# MicroController.net
KiCad netlist of a schematic drawn in Altium Designer
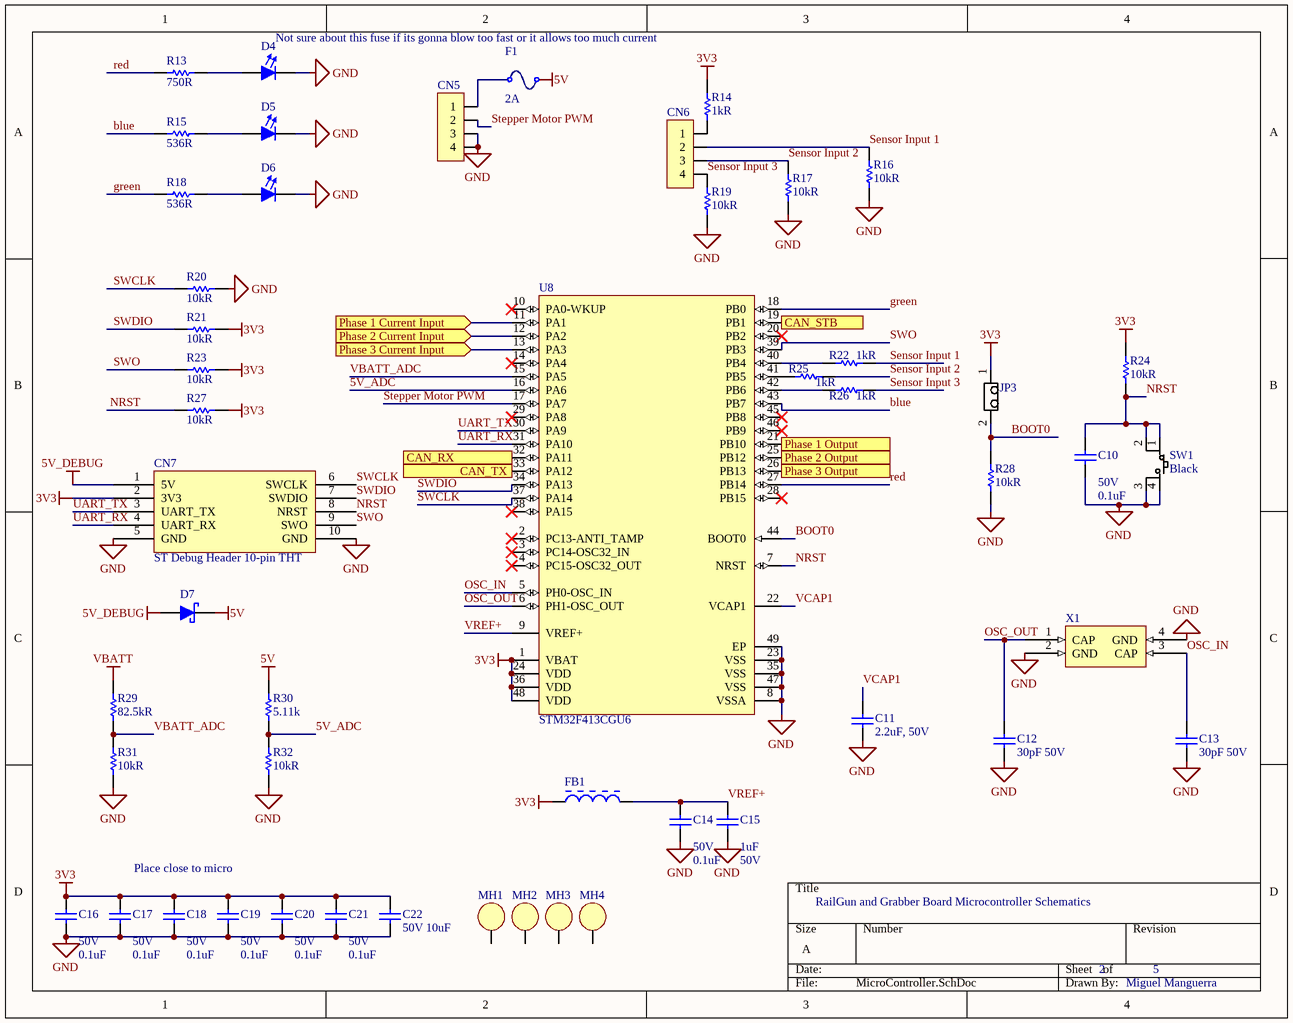
[diagram p0: MicroController.SchDoc]

(export (version "E")
  (design (tool "Eeschema 10.0.6"))
  (components
    (comp (ref "C10")
      (value "CL10B104JB8NNNC")
      (footprint "FP-CL10-0_1-MFG")
      (description "CAP CER 0.1UF 50V X7R 0603")
      (fields
        (field (name "TOLERANCE") "5%")
        (field (name "VOLTAGE") "50V")
        (field (name "CAPACITANCE") "0.1uF")
      )
      (libsource (lib "AUVIC") (part "CAP-NP-2"))
    )
    (comp (ref "C11")
      (value "2.2uF, 50V")
      (footprint "CAPC1608N(0603\")")
      (description "Capacitor, Ceramic, 50V, 10%, 0603 SMD, X5R")
      (fields (field (name "MADE BY") "*") (field (name "PUBLISHER") "AUVic"))
      (libsource (lib "") (part "Symbol_7"))
    )
    (comp (ref "C12")
      (value "30pF 50V")
      (footprint "CAPC1608N(0603\")")
      (description "Capacitor, Ceramic, 50V, +/-1%, 0603 SMD, C0G")
      (fields (field (name "MADE BY") "Andy Bates") (field (name "PUBLISHER") "AUVic"))
      (libsource (lib "") (part "Symbol_8"))
    )
    (comp (ref "C13")
      (value "30pF 50V")
      (footprint "CAPC1608N(0603\")")
      (description "Capacitor, Ceramic, 50V, +/-1%, 0603 SMD, C0G")
      (fields (field (name "MADE BY") "Andy Bates") (field (name "PUBLISHER") "AUVic"))
      (libsource (lib "") (part "Symbol_8"))
    )
    (comp (ref "C14")
      (value "CL10B104JB8NNNC")
      (footprint "FP-CL10-0_1-MFG")
      (description "CAP CER 0.1UF 50V X7R 0603")
      (fields
        (field (name "TOLERANCE") "5%")
        (field (name "VOLTAGE") "50V")
        (field (name "CAPACITANCE") "0.1uF")
      )
      (libsource (lib "AUVIC") (part "CAP-NP-2"))
    )
    (comp (ref "C15")
      (value "CL21B105KBFNNNG")
      (footprint "0803 CAP")
      (description "SAMSUNG ELECTRO-MECHANICS - CL21B105KBFNNNG - MLCC CAPACITORS")
      (fields
        (field (name "TOLERANCE") "10%")
        (field (name "CAPACITANCE") "1uF")
        (field (name "VOLTAGE") "50V")
      )
      (libsource (lib "") (part "Symbol_4"))
    )
    (comp (ref "C16")
      (value "CL10B104JB8NNNC")
      (footprint "FP-CL10-0_1-MFG")
      (description "CAP CER 0.1UF 50V X7R 0603")
      (fields
        (field (name "TOLERANCE") "5%")
        (field (name "VOLTAGE") "50V")
        (field (name "CAPACITANCE") "0.1uF")
      )
      (libsource (lib "AUVIC") (part "CAP-NP-2"))
    )
    (comp (ref "C17")
      (value "CL10B104JB8NNNC")
      (footprint "FP-CL10-0_1-MFG")
      (description "CAP CER 0.1UF 50V X7R 0603")
      (fields
        (field (name "TOLERANCE") "5%")
        (field (name "VOLTAGE") "50V")
        (field (name "CAPACITANCE") "0.1uF")
      )
      (libsource (lib "AUVIC") (part "CAP-NP-2"))
    )
    (comp (ref "C18")
      (value "CL10B104JB8NNNC")
      (footprint "FP-CL10-0_1-MFG")
      (description "CAP CER 0.1UF 50V X7R 0603")
      (fields
        (field (name "TOLERANCE") "5%")
        (field (name "VOLTAGE") "50V")
        (field (name "CAPACITANCE") "0.1uF")
      )
      (libsource (lib "AUVIC") (part "CAP-NP-2"))
    )
    (comp (ref "C19")
      (value "CL10B104JB8NNNC")
      (footprint "FP-CL10-0_1-MFG")
      (description "CAP CER 0.1UF 50V X7R 0603")
      (fields
        (field (name "TOLERANCE") "5%")
        (field (name "VOLTAGE") "50V")
        (field (name "CAPACITANCE") "0.1uF")
      )
      (libsource (lib "AUVIC") (part "CAP-NP-2"))
    )
    (comp (ref "C20")
      (value "CL10B104JB8NNNC")
      (footprint "FP-CL10-0_1-MFG")
      (description "CAP CER 0.1UF 50V X7R 0603")
      (fields
        (field (name "TOLERANCE") "5%")
        (field (name "VOLTAGE") "50V")
        (field (name "CAPACITANCE") "0.1uF")
      )
      (libsource (lib "AUVIC") (part "CAP-NP-2"))
    )
    (comp (ref "C21")
      (value "CL10B104JB8NNNC")
      (footprint "FP-CL10-0_1-MFG")
      (description "CAP CER 0.1UF 50V X7R 0603")
      (fields
        (field (name "TOLERANCE") "5%")
        (field (name "VOLTAGE") "50V")
        (field (name "CAPACITANCE") "0.1uF")
      )
      (libsource (lib "AUVIC") (part "CAP-NP-2"))
    )
    (comp (ref "C22")
      (value "50V 10uF")
      (footprint "CAPC3216X180X50LL20T30")
      (description "Cap Ceramic 10uF 50V X7R 10% Pad SMD 1206 125°C T/R")
      (fields (field (name "TOLERANCE") "10%"))
      (libsource (lib "AUVIC") (part "CAP-NP-2"))
    )
    (comp (ref "CN5")
      (value "Header, Male, 1x4, RA, Pitch 0.1\" (2.54mm)")
      (footprint "HEADER, MALE, SHROUDED, 4x1, PITCH 0.1\" (2.54mm), RA")
      (description "Connector Header Through Hole, Right Angle 4 position 0.100\" (2.54mm)")
      (fields (field (name "CREATED BY") "Miguel Manguerra"))
      (libsource (lib "") (part "Symbol_3"))
    )
    (comp (ref "CN6")
      (value "Header, Male, 1x4, RA, Pitch 0.1\" (2.54mm)")
      (footprint "HEADER, MALE, SHROUDED, 4x1, PITCH 0.1\" (2.54mm), RA")
      (description "Connector Header Through Hole, Right Angle 4 position 0.100\" (2.54mm)")
      (fields (field (name "CREATED BY") "Miguel Manguerra"))
      (libsource (lib "") (part "Symbol_3"))
    )
    (comp (ref "CN7")
      (value "ST Debug Header 10-pin THT")
      (footprint "10-pin shrouded header THT")
      (description "CONN HEADER VERT 10POS 2.54MM")
      (libsource (lib "AUVIC") (part "ST Debug Header 10-pin"))
    )
    (comp (ref "D4")
      (value "LSQ976-NR-1")
      (footprint "FP-LB_Q39E-MFG")
      (description "LED Red 645nm 2-Pin Chip 0603(1608Metric) T/R")
      (libsource (lib "AUVIC") (part "Symbol"))
    )
    (comp (ref "D5")
      (value "LBQ39E-N1OO-35-1")
      (footprint "FP-LB_Q39E-MFG")
      (description "LED BLUE DIFFUSED 0603 SMD")
      (libsource (lib "AUVIC") (part "Symbol"))
    )
    (comp (ref "D6")
      (value "LT Q39G-Q1OO-25-1")
      (footprint "FP-LB_Q39E-MFG")
      (description "LED GREEN DIFFUSED 0603 SMD")
      (libsource (lib "AUVIC") (part "Symbol"))
    )
    (comp (ref "D7")
      (value "CUS08F30,H3F")
      (footprint "SC-76")
      (description "Diode Schottky 30V 800mA Surface Mount USC")
      (libsource (lib "") (part "Symbol_6"))
    )
    (comp (ref "F1")
      (value "SMD Fuse, 2A, 63V,")
      (footprint "1206 SMD")
      (fields (field (name "CURRENT") "2A") (field (name "CREATED BY") "Poorna Chander Kalidas"))
      (libsource (lib "") (part "Symbol_2"))
    )
    (comp (ref "FB1")
      (value "BLM18AG601SN1D")
      (footprint "MURA-BLM18-F-H1-CHIP-2_V")
      (fields (field (name "TOLERANCE") "25%"))
      (libsource (lib "AUVIC") (part "MURA-FB-2"))
    )
    (comp (ref "JP3")
      (value "1x2 Male Header")
      (footprint "2X1 Males Header")
      (fields (field (name "MADE BY") "Andy Bates"))
      (libsource (lib "AUVIC") (part "1x2 Male Header"))
    )
    (comp (ref "MH1")
      (value "Mount_Hole_3mm")
      (footprint "Mount-Hole_3mm")
      (description "Mounting hold for M3 hex standoff")
      (libsource (lib "AUVIC") (part "Mount_Hole_3mm"))
    )
    (comp (ref "MH2")
      (value "Mount_Hole_3mm")
      (footprint "Mount-Hole_3mm")
      (description "Mounting hold for M3 hex standoff")
      (libsource (lib "AUVIC") (part "Mount_Hole_3mm"))
    )
    (comp (ref "MH3")
      (value "Mount_Hole_3mm")
      (footprint "Mount-Hole_3mm")
      (description "Mounting hold for M3 hex standoff")
      (libsource (lib "AUVIC") (part "Mount_Hole_3mm"))
    )
    (comp (ref "MH4")
      (value "Mount_Hole_3mm")
      (footprint "Mount-Hole_3mm")
      (description "Mounting hold for M3 hex standoff")
      (libsource (lib "AUVIC") (part "Mount_Hole_3mm"))
    )
    (comp (ref "R13")
      (value "750R")
      (footprint "RESC0603(1608)_N")
      (description "Res Thick Film 0603 750 Ohm 1% 0.1W(1/10W) ±100ppm/C Epoxy SMD T/R")
      (fields (field (name "TOLERANCE") "1%"))
      (libsource (lib "AUVIC") (part "RES"))
    )
    (comp (ref "R14")
      (value "1kR")
      (footprint "RESC1608N(0603\")")
      (description "1kR, 1%, 1/10W , 0603, SMD")
      (fields (field (name "PUBLISHER") "AUVic") (field (name "CREATED BY") "Andy Bates"))
      (libsource (lib "") (part "Symbol_1"))
    )
    (comp (ref "R15")
      (value "536R")
      (footprint "RESC1608X55X30LL15T15")
      (description "SMD Chip Resistor, 0603 [1608 Metric], 536 ohm, ERJ3EK Series, 75 V, Thick Film, 100 mW")
      (fields (field (name "TOLERANCE") "1%"))
      (libsource (lib "AUVIC") (part "RES"))
    )
    (comp (ref "R16")
      (value "10kR")
      (footprint "RESC1608N(0603\")")
      (description "10kR, 1%, 1/10W, 0603 SMD")
      (fields (field (name "MADE BY") "Ashwin Sira"))
      (libsource (lib "") (part "Symbol_1"))
    )
    (comp (ref "R17")
      (value "10kR")
      (footprint "RESC1608N(0603\")")
      (description "10kR, 1%, 1/10W, 0603 SMD")
      (fields (field (name "MADE BY") "Ashwin Sira"))
      (libsource (lib "") (part "Symbol_1"))
    )
    (comp (ref "R18")
      (value "536R")
      (footprint "RESC1608X55X30LL15T15")
      (description "SMD Chip Resistor, 0603 [1608 Metric], 536 ohm, ERJ3EK Series, 75 V, Thick Film, 100 mW")
      (fields (field (name "TOLERANCE") "1%"))
      (libsource (lib "AUVIC") (part "RES"))
    )
    (comp (ref "R19")
      (value "10kR")
      (footprint "RESC1608N(0603\")")
      (description "10kR, 1%, 1/10W, 0603 SMD")
      (fields (field (name "MADE BY") "Ashwin Sira"))
      (libsource (lib "") (part "Symbol_1"))
    )
    (comp (ref "R20")
      (value "10kR")
      (footprint "RESC1608N(0603\")")
      (description "10kR, 1%, 1/10W, 0603 SMD")
      (fields (field (name "MADE BY") "Ashwin Sira"))
      (libsource (lib "") (part "Symbol_1"))
    )
    (comp (ref "R21")
      (value "10kR")
      (footprint "RESC1608N(0603\")")
      (description "10kR, 1%, 1/10W, 0603 SMD")
      (fields (field (name "MADE BY") "Ashwin Sira"))
      (libsource (lib "") (part "Symbol_1"))
    )
    (comp (ref "R22")
      (value "1kR")
      (footprint "RESC1608N(0603\")")
      (description "1kR, 1%, 1/10W , 0603, SMD")
      (fields (field (name "PUBLISHER") "AUVic") (field (name "CREATED BY") "Andy Bates"))
      (libsource (lib "") (part "Symbol_1"))
    )
    (comp (ref "R23")
      (value "10kR")
      (footprint "RESC1608N(0603\")")
      (description "10kR, 1%, 1/10W, 0603 SMD")
      (fields (field (name "MADE BY") "Ashwin Sira"))
      (libsource (lib "") (part "Symbol_1"))
    )
    (comp (ref "R24")
      (value "10kR")
      (footprint "RESC1608N(0603\")")
      (description "10kR, 1%, 1/10W, 0603 SMD")
      (fields (field (name "MADE BY") "Ashwin Sira"))
      (libsource (lib "") (part "Symbol_1"))
    )
    (comp (ref "R25")
      (value "1kR")
      (footprint "RESC1608N(0603\")")
      (description "1kR, 1%, 1/10W , 0603, SMD")
      (fields (field (name "PUBLISHER") "AUVic") (field (name "CREATED BY") "Andy Bates"))
      (libsource (lib "") (part "Symbol_1"))
    )
    (comp (ref "R26")
      (value "1kR")
      (footprint "RESC1608N(0603\")")
      (description "1kR, 1%, 1/10W , 0603, SMD")
      (fields (field (name "PUBLISHER") "AUVic") (field (name "CREATED BY") "Andy Bates"))
      (libsource (lib "") (part "Symbol_1"))
    )
    (comp (ref "R27")
      (value "10kR")
      (footprint "RESC1608N(0603\")")
      (description "10kR, 1%, 1/10W, 0603 SMD")
      (fields (field (name "MADE BY") "Ashwin Sira"))
      (libsource (lib "") (part "Symbol_1"))
    )
    (comp (ref "R28")
      (value "10kR")
      (footprint "RESC1608N(0603\")")
      (description "10kR, 1%, 1/10W, 0603 SMD")
      (fields (field (name "MADE BY") "Ashwin Sira"))
      (libsource (lib "") (part "Symbol_1"))
    )
    (comp (ref "R29")
      (value "ERJ-3EKF8252V")
      (footprint "RESC1608X55X30LL15T15")
      (description "RES SMD 82.5K OHM 1% 1/10W 0603")
      (fields (field (name "RESISTANCE") "82.5kR") (field (name "TOLERANCE") "1%"))
      (libsource (lib "AUVIC") (part "RES"))
    )
    (comp (ref "R30")
      (value "5.11k")
      (footprint "RESC1608N(0603\")")
      (description "Resistance, Tolerance, Power, 0603, SMD/THT")
      (fields
        (field (name "Comment") "5.11kR, 1%, 1/10W, 0603, SMD")
        (field (name "PUBLISHER") "AUVic")
        (field (name "CREATED BY") "Jordan Day")
      )
      (libsource (lib "") (part "Symbol_1"))
    )
    (comp (ref "R31")
      (value "RC0603FR-0710KL")
      (footprint "RESC1608X55X25NL10T15")
      (description "Res General Purpose Thick Film 0603 10K Ohm 1% 1/10W ±100ppm/°C Molded SMD Paper T/R")
      (fields (field (name "RESISTANCE") "10kR") (field (name "TOLERANCE") "1%"))
      (libsource (lib "AUVIC") (part "RES-2"))
    )
    (comp (ref "R32")
      (value "RC0603FR-0710KL")
      (footprint "RESC1608X55X25NL10T15")
      (description "Res General Purpose Thick Film 0603 10K Ohm 1% 1/10W ±100ppm/°C Molded SMD Paper T/R")
      (fields (field (name "RESISTANCE") "10kR") (field (name "TOLERANCE") "1%"))
      (libsource (lib "AUVIC") (part "RES-2"))
    )
    (comp (ref "SW1")
      (value "PTS645SL43SMTR92LFS")
      (footprint "4-SPST-NO")
      (description "Black Switch Tactile N.O. SPST Round Button Gull Wing 0.05A 12VDC 100000Cycles 1.27N SMD T/R")
      (fields (field (name "BUTTON COLOUR") "Black"))
      (libsource (lib "") (part "Symbol_5"))
    )
    (comp (ref "U8")
      (value "STM32F413CGU6")
      (footprint "STM-UFQFPN48_N")
      (description "MCU 32-Bit STM32 ARM Cortex M4 RISC 1MB Flash 1.8V/2.5V/3.3V 48-Pin UFQFPN Tray")
      (libsource (lib "AUVIC") (part "MC-ARM-STM32F411-UFQFPN48"))
    )
    (comp (ref "X1")
      (value "CRYSTAL 8.0MHZ 16PF SMD")
      (footprint "QFN250P750X520X140_HS-5M")
      (description "8MHz ±30ppm Crystal 16pF 80 Ohms 4-SMD, No Lead")
      (libsource (lib "AUVIC") (part "LFXTAL026380REEL"))
    )
  )
  (nets
    (net (code "1") (name "/5V_ADC") (class "Default")
      (node (ref "R30") (pin "2") (pinfunction "2_2") (pintype "passive"))
      (node (ref "R32") (pin "1") (pinfunction "1_1") (pintype "passive"))
      (node (ref "U8") (pin "16") (pinfunction "PA6_16") (pintype "bidirectional"))
    )
    (net (code "2") (name "/BOOT0") (class "Default")
      (node (ref "JP3") (pin "2") (pinfunction "2_2") (pintype "passive"))
      (node (ref "R28") (pin "1") (pinfunction "1_1") (pintype "passive"))
      (node (ref "U8") (pin "44") (pinfunction "BOOT0_44") (pintype "input"))
    )
    (net (code "3") (name "/CAN_RX") (class "Default")
      (node (ref "U8") (pin "32") (pinfunction "PA11_32") (pintype "bidirectional"))
    )
    (net (code "4") (name "/CAN_STB") (class "Default")
      (node (ref "U8") (pin "19") (pinfunction "PB1_19") (pintype "bidirectional"))
    )
    (net (code "5") (name "/CAN_TX") (class "Default")
      (node (ref "U8") (pin "33") (pinfunction "PA12_33") (pintype "bidirectional"))
    )
    (net (code "6") (name "/NRST") (class "Default")
      (node (ref "C10") (pin "1") (pinfunction "1_1") (pintype "passive"))
      (node (ref "CN7") (pin "8") (pinfunction "NRST_8") (pintype "passive"))
      (node (ref "R24") (pin "2") (pinfunction "2_2") (pintype "passive"))
      (node (ref "R27") (pin "2") (pinfunction "2_2") (pintype "passive"))
      (node (ref "SW1") (pin "1") (pinfunction "1_1") (pintype "passive"))
      (node (ref "SW1") (pin "2") (pinfunction "2_2") (pintype "passive"))
      (node (ref "U8") (pin "7") (pinfunction "NRST_7") (pintype "bidirectional"))
    )
    (net (code "7") (name "/OSC_IN") (class "Default")
      (node (ref "C13") (pin "1") (pinfunction "1_1") (pintype "passive"))
      (node (ref "U8") (pin "5") (pinfunction "PH0-OSC_IN_5") (pintype "bidirectional"))
      (node (ref "X1") (pin "3") (pinfunction "CAP_3") (pintype "input"))
    )
    (net (code "8") (name "/OSC_OUT") (class "Default")
      (node (ref "C12") (pin "1") (pinfunction "1_1") (pintype "passive"))
      (node (ref "U8") (pin "6") (pinfunction "PH1-OSC_OUT_6") (pintype "bidirectional"))
      (node (ref "X1") (pin "1") (pinfunction "CAP_1") (pintype "input"))
    )
    (net (code "9") (name "/Phase 1 Current Input") (class "Default")
      (node (ref "U8") (pin "11") (pinfunction "PA1_11") (pintype "bidirectional"))
    )
    (net (code "10") (name "/Phase 1 Output") (class "Default")
      (node (ref "U8") (pin "21") (pinfunction "PB10_21") (pintype "bidirectional"))
    )
    (net (code "11") (name "/Phase 2 Current Input") (class "Default")
      (node (ref "U8") (pin "12") (pinfunction "PA2_12") (pintype "bidirectional"))
    )
    (net (code "12") (name "/Phase 2 Output") (class "Default")
      (node (ref "U8") (pin "25") (pinfunction "PB12_25") (pintype "bidirectional"))
    )
    (net (code "13") (name "/Phase 3 Current Input") (class "Default")
      (node (ref "U8") (pin "13") (pinfunction "PA3_13") (pintype "bidirectional"))
    )
    (net (code "14") (name "/Phase 3 Output") (class "Default")
      (node (ref "U8") (pin "26") (pinfunction "PB13_26") (pintype "bidirectional"))
    )
    (net (code "15") (name "/SWCLK") (class "Default")
      (node (ref "CN7") (pin "6") (pinfunction "SWCLK_6") (pintype "passive"))
      (node (ref "R20") (pin "2") (pinfunction "2_2") (pintype "passive"))
      (node (ref "U8") (pin "37") (pinfunction "PA14_37") (pintype "bidirectional"))
    )
    (net (code "16") (name "/SWDIO") (class "Default")
      (node (ref "CN7") (pin "7") (pinfunction "SWDIO_7") (pintype "passive"))
      (node (ref "R21") (pin "2") (pinfunction "2_2") (pintype "passive"))
      (node (ref "U8") (pin "34") (pinfunction "PA13_34") (pintype "bidirectional"))
    )
    (net (code "17") (name "/SWO") (class "Default")
      (node (ref "CN7") (pin "9") (pinfunction "SWO_9") (pintype "passive"))
      (node (ref "R23") (pin "2") (pinfunction "2_2") (pintype "passive"))
      (node (ref "U8") (pin "39") (pinfunction "PB3_39") (pintype "bidirectional"))
    )
    (net (code "18") (name "/Sensor Input 1") (class "Default")
      (node (ref "CN6") (pin "2") (pinfunction "2_2") (pintype "passive"))
      (node (ref "R16") (pin "1") (pinfunction "1_1") (pintype "passive"))
      (node (ref "R22") (pin "2") (pinfunction "2_2") (pintype "passive"))
    )
    (net (code "19") (name "/Sensor Input 2") (class "Default")
      (node (ref "CN6") (pin "3") (pinfunction "3_3") (pintype "passive"))
      (node (ref "R17") (pin "1") (pinfunction "1_1") (pintype "passive"))
      (node (ref "R25") (pin "2") (pinfunction "2_2") (pintype "passive"))
    )
    (net (code "20") (name "/Sensor Input 3") (class "Default")
      (node (ref "CN6") (pin "4") (pinfunction "4_4") (pintype "passive"))
      (node (ref "R19") (pin "1") (pinfunction "1_1") (pintype "passive"))
      (node (ref "R26") (pin "2") (pinfunction "2_2") (pintype "passive"))
    )
    (net (code "21") (name "/Stepper Motor PWM") (class "Default")
      (node (ref "CN5") (pin "2") (pinfunction "2_2") (pintype "passive"))
      (node (ref "U8") (pin "17") (pinfunction "PA7_17") (pintype "bidirectional"))
    )
    (net (code "22") (name "/UART_RX") (class "Default")
      (node (ref "CN7") (pin "4") (pinfunction "UART_RX_4") (pintype "passive"))
      (node (ref "U8") (pin "31") (pinfunction "PA10_31") (pintype "bidirectional"))
    )
    (net (code "23") (name "/UART_TX") (class "Default")
      (node (ref "CN7") (pin "3") (pinfunction "UART_TX_3") (pintype "passive"))
      (node (ref "U8") (pin "30") (pinfunction "PA9_30") (pintype "bidirectional"))
    )
    (net (code "24") (name "/VBATT_ADC") (class "Default")
      (node (ref "R29") (pin "2") (pinfunction "2_2") (pintype "passive"))
      (node (ref "R31") (pin "1") (pinfunction "1_1") (pintype "passive"))
      (node (ref "U8") (pin "15") (pinfunction "PA5_15") (pintype "bidirectional"))
    )
    (net (code "25") (name "/VCAP1") (class "Default")
      (node (ref "C11") (pin "1") (pinfunction "Anode_1") (pintype "passive"))
      (node (ref "U8") (pin "22") (pinfunction "VCAP1_22") (pintype "passive"))
    )
    (net (code "26") (name "/VREF+") (class "Default")
      (node (ref "C14") (pin "1") (pinfunction "1_1") (pintype "passive"))
      (node (ref "C15") (pin "1") (pinfunction "1_1") (pintype "passive"))
      (node (ref "FB1") (pin "2") (pinfunction "2_2") (pintype "passive"))
      (node (ref "U8") (pin "9") (pinfunction "VREF+_9") (pintype "power_in"))
    )
    (net (code "27") (name "/blue") (class "Default")
      (node (ref "R15") (pin "1") (pinfunction "1_1") (pintype "passive"))
      (node (ref "U8") (pin "43") (pinfunction "PB7_43") (pintype "bidirectional"))
    )
    (net (code "28") (name "/green") (class "Default")
      (node (ref "R18") (pin "1") (pinfunction "1_1") (pintype "passive"))
      (node (ref "U8") (pin "18") (pinfunction "PB0_18") (pintype "bidirectional"))
    )
    (net (code "29") (name "/red") (class "Default")
      (node (ref "R13") (pin "1") (pinfunction "1_1") (pintype "passive"))
      (node (ref "U8") (pin "27") (pinfunction "PB14_27") (pintype "bidirectional"))
    )
    (net (code "30") (name "3V3") (class "Default")
      (node (ref "C16") (pin "1") (pinfunction "1_1") (pintype "passive"))
      (node (ref "C17") (pin "1") (pinfunction "1_1") (pintype "passive"))
      (node (ref "C18") (pin "1") (pinfunction "1_1") (pintype "passive"))
      (node (ref "C19") (pin "1") (pinfunction "1_1") (pintype "passive"))
      (node (ref "C20") (pin "1") (pinfunction "1_1") (pintype "passive"))
      (node (ref "C21") (pin "1") (pinfunction "1_1") (pintype "passive"))
      (node (ref "C22") (pin "1") (pinfunction "1_1") (pintype "passive"))
      (node (ref "CN7") (pin "2") (pinfunction "3V3_2") (pintype "passive"))
      (node (ref "FB1") (pin "1") (pinfunction "1_1") (pintype "passive"))
      (node (ref "JP3") (pin "1") (pinfunction "1_1") (pintype "passive"))
      (node (ref "R14") (pin "1") (pinfunction "1_1") (pintype "passive"))
      (node (ref "R21") (pin "1") (pinfunction "1_1") (pintype "passive"))
      (node (ref "R23") (pin "1") (pinfunction "1_1") (pintype "passive"))
      (node (ref "R24") (pin "1") (pinfunction "1_1") (pintype "passive"))
      (node (ref "R27") (pin "1") (pinfunction "1_1") (pintype "passive"))
      (node (ref "U8") (pin "1") (pinfunction "VBAT_1") (pintype "power_in"))
      (node (ref "U8") (pin "24") (pinfunction "VDD_24") (pintype "power_in"))
      (node (ref "U8") (pin "36") (pinfunction "VDD_36") (pintype "power_in"))
      (node (ref "U8") (pin "48") (pinfunction "VDD_48") (pintype "power_in"))
    )
    (net (code "31") (name "5V") (class "Default")
      (node (ref "D7") (pin "K") (pinfunction "Cathode_K") (pintype "passive"))
      (node (ref "F1") (pin "2") (pinfunction "2_2") (pintype "passive"))
      (node (ref "R30") (pin "1") (pinfunction "1_1") (pintype "passive"))
    )
    (net (code "32") (name "5V_DEBUG") (class "Default")
      (node (ref "CN7") (pin "1") (pinfunction "5V_1") (pintype "passive"))
      (node (ref "D7") (pin "A") (pinfunction "Anode_A") (pintype "passive"))
    )
    (net (code "33") (name "GND") (class "Default")
      (node (ref "C10") (pin "2") (pinfunction "2_2") (pintype "passive"))
      (node (ref "C11") (pin "2") (pinfunction "Cathode_2") (pintype "passive"))
      (node (ref "C12") (pin "2") (pinfunction "2_2") (pintype "passive"))
      (node (ref "C13") (pin "2") (pinfunction "2_2") (pintype "passive"))
      (node (ref "C14") (pin "2") (pinfunction "2_2") (pintype "passive"))
      (node (ref "C15") (pin "2") (pinfunction "2_2") (pintype "passive"))
      (node (ref "C16") (pin "2") (pinfunction "2_2") (pintype "passive"))
      (node (ref "C17") (pin "2") (pinfunction "2_2") (pintype "passive"))
      (node (ref "C18") (pin "2") (pinfunction "2_2") (pintype "passive"))
      (node (ref "C19") (pin "2") (pinfunction "2_2") (pintype "passive"))
      (node (ref "C20") (pin "2") (pinfunction "2_2") (pintype "passive"))
      (node (ref "C21") (pin "2") (pinfunction "2_2") (pintype "passive"))
      (node (ref "C22") (pin "2") (pinfunction "2_2") (pintype "passive"))
      (node (ref "CN5") (pin "3") (pinfunction "3_3") (pintype "passive"))
      (node (ref "CN5") (pin "4") (pinfunction "4_4") (pintype "passive"))
      (node (ref "CN7") (pin "10") (pinfunction "GND_10") (pintype "passive"))
      (node (ref "CN7") (pin "5") (pinfunction "GND_5") (pintype "passive"))
      (node (ref "D4") (pin "1") (pinfunction "Cathode_1") (pintype "passive"))
      (node (ref "D5") (pin "1") (pinfunction "Cathode_1") (pintype "passive"))
      (node (ref "D6") (pin "1") (pinfunction "Cathode_1") (pintype "passive"))
      (node (ref "R16") (pin "2") (pinfunction "2_2") (pintype "passive"))
      (node (ref "R17") (pin "2") (pinfunction "2_2") (pintype "passive"))
      (node (ref "R19") (pin "2") (pinfunction "2_2") (pintype "passive"))
      (node (ref "R20") (pin "1") (pinfunction "1_1") (pintype "passive"))
      (node (ref "R28") (pin "2") (pinfunction "2_2") (pintype "passive"))
      (node (ref "R31") (pin "2") (pinfunction "2_2") (pintype "passive"))
      (node (ref "R32") (pin "2") (pinfunction "2_2") (pintype "passive"))
      (node (ref "SW1") (pin "3") (pinfunction "3_3") (pintype "passive"))
      (node (ref "SW1") (pin "4") (pinfunction "4_4") (pintype "passive"))
      (node (ref "U8") (pin "23") (pinfunction "VSS_23") (pintype "power_in"))
      (node (ref "U8") (pin "35") (pinfunction "VSS_35") (pintype "power_in"))
      (node (ref "U8") (pin "47") (pinfunction "VSS_47") (pintype "power_in"))
      (node (ref "U8") (pin "49") (pinfunction "EP_49") (pintype "power_in"))
      (node (ref "U8") (pin "8") (pinfunction "VSSA_8") (pintype "power_in"))
      (node (ref "X1") (pin "2") (pinfunction "GND_2") (pintype "input"))
      (node (ref "X1") (pin "4") (pinfunction "GND_4") (pintype "input"))
    )
    (net (code "34") (name "Net-(CN5-Pad1)") (class "Default")
      (node (ref "CN5") (pin "1") (pinfunction "1_1") (pintype "passive"))
      (node (ref "F1") (pin "1") (pinfunction "1_1") (pintype "passive"))
    )
    (net (code "35") (name "Net-(CN6-Pad1)") (class "Default")
      (node (ref "CN6") (pin "1") (pinfunction "1_1") (pintype "passive"))
      (node (ref "R14") (pin "2") (pinfunction "2_2") (pintype "passive"))
    )
    (net (code "36") (name "Net-(D4-Anode)") (class "Default")
      (node (ref "D4") (pin "2") (pinfunction "Anode_2") (pintype "passive"))
      (node (ref "R13") (pin "2") (pinfunction "2_2") (pintype "passive"))
    )
    (net (code "37") (name "Net-(D5-Anode)") (class "Default")
      (node (ref "D5") (pin "2") (pinfunction "Anode_2") (pintype "passive"))
      (node (ref "R15") (pin "2") (pinfunction "2_2") (pintype "passive"))
    )
    (net (code "38") (name "Net-(D6-Anode)") (class "Default")
      (node (ref "D6") (pin "2") (pinfunction "Anode_2") (pintype "passive"))
      (node (ref "R18") (pin "2") (pinfunction "2_2") (pintype "passive"))
    )
    (net (code "39") (name "Net-(U8-PB4)") (class "Default")
      (node (ref "R22") (pin "1") (pinfunction "1_1") (pintype "passive"))
      (node (ref "U8") (pin "40") (pinfunction "PB4_40") (pintype "bidirectional"))
    )
    (net (code "40") (name "Net-(U8-PB5)") (class "Default")
      (node (ref "R25") (pin "1") (pinfunction "1_1") (pintype "passive"))
      (node (ref "U8") (pin "41") (pinfunction "PB5_41") (pintype "bidirectional"))
    )
    (net (code "41") (name "Net-(U8-PB6)") (class "Default")
      (node (ref "R26") (pin "1") (pinfunction "1_1") (pintype "passive"))
      (node (ref "U8") (pin "42") (pinfunction "PB6_42") (pintype "bidirectional"))
    )
    (net (code "42") (name "VBATT") (class "Default")
      (node (ref "R29") (pin "1") (pinfunction "1_1") (pintype "passive"))
    )
    (net (code "43") (name "unconnected-(MH1-Pad1)") (class "Default")
      (node (ref "MH1") (pin "1") (pinfunction "1_1") (pintype "passive"))
    )
    (net (code "44") (name "unconnected-(MH2-Pad1)") (class "Default")
      (node (ref "MH2") (pin "1") (pinfunction "1_1") (pintype "passive"))
    )
    (net (code "45") (name "unconnected-(MH3-Pad1)") (class "Default")
      (node (ref "MH3") (pin "1") (pinfunction "1_1") (pintype "passive"))
    )
    (net (code "46") (name "unconnected-(MH4-Pad1)") (class "Default")
      (node (ref "MH4") (pin "1") (pinfunction "1_1") (pintype "passive"))
    )
    (net (code "47") (name "unconnected-(U8-PA0-WKUP-Pad10)") (class "Default")
      (node (ref "U8") (pin "10") (pinfunction "PA0-WKUP_10") (pintype "bidirectional+no_connect"))
    )
    (net (code "48") (name "unconnected-(U8-PA4-Pad14)") (class "Default")
      (node (ref "U8") (pin "14") (pinfunction "PA4_14") (pintype "bidirectional+no_connect"))
    )
    (net (code "49") (name "unconnected-(U8-PA8-Pad29)") (class "Default")
      (node (ref "U8") (pin "29") (pinfunction "PA8_29") (pintype "bidirectional+no_connect"))
    )
    (net (code "50") (name "unconnected-(U8-PA15-Pad38)") (class "Default")
      (node (ref "U8") (pin "38") (pinfunction "PA15_38") (pintype "bidirectional+no_connect"))
    )
    (net (code "51") (name "unconnected-(U8-PB2-Pad20)") (class "Default")
      (node (ref "U8") (pin "20") (pinfunction "PB2_20") (pintype "bidirectional+no_connect"))
    )
    (net (code "52") (name "unconnected-(U8-PB8-Pad45)") (class "Default")
      (node (ref "U8") (pin "45") (pinfunction "PB8_45") (pintype "bidirectional+no_connect"))
    )
    (net (code "53") (name "unconnected-(U8-PB9-Pad46)") (class "Default")
      (node (ref "U8") (pin "46") (pinfunction "PB9_46") (pintype "bidirectional+no_connect"))
    )
    (net (code "54") (name "unconnected-(U8-PB15-Pad28)") (class "Default")
      (node (ref "U8") (pin "28") (pinfunction "PB15_28") (pintype "bidirectional+no_connect"))
    )
    (net (code "55") (name "unconnected-(U8-PC13-ANTI_TAMP-Pad2)") (class "Default")
      (node (ref "U8") (pin "2") (pinfunction "PC13-ANTI_TAMP_2") (pintype "bidirectional+no_connect"))
    )
    (net (code "56") (name "unconnected-(U8-PC14-OSC32_IN-Pad3)") (class "Default")
      (node (ref "U8") (pin "3") (pinfunction "PC14-OSC32_IN_3") (pintype "bidirectional+no_connect"))
    )
    (net (code "57") (name "unconnected-(U8-PC15-OSC32_OUT-Pad4)") (class "Default")
      (node (ref "U8") (pin "4") (pinfunction "PC15-OSC32_OUT_4") (pintype "bidirectional+no_connect"))
    )
  )
)
